# test_npf.net
KiCad netlist of a schematic drawn in Altium Designer
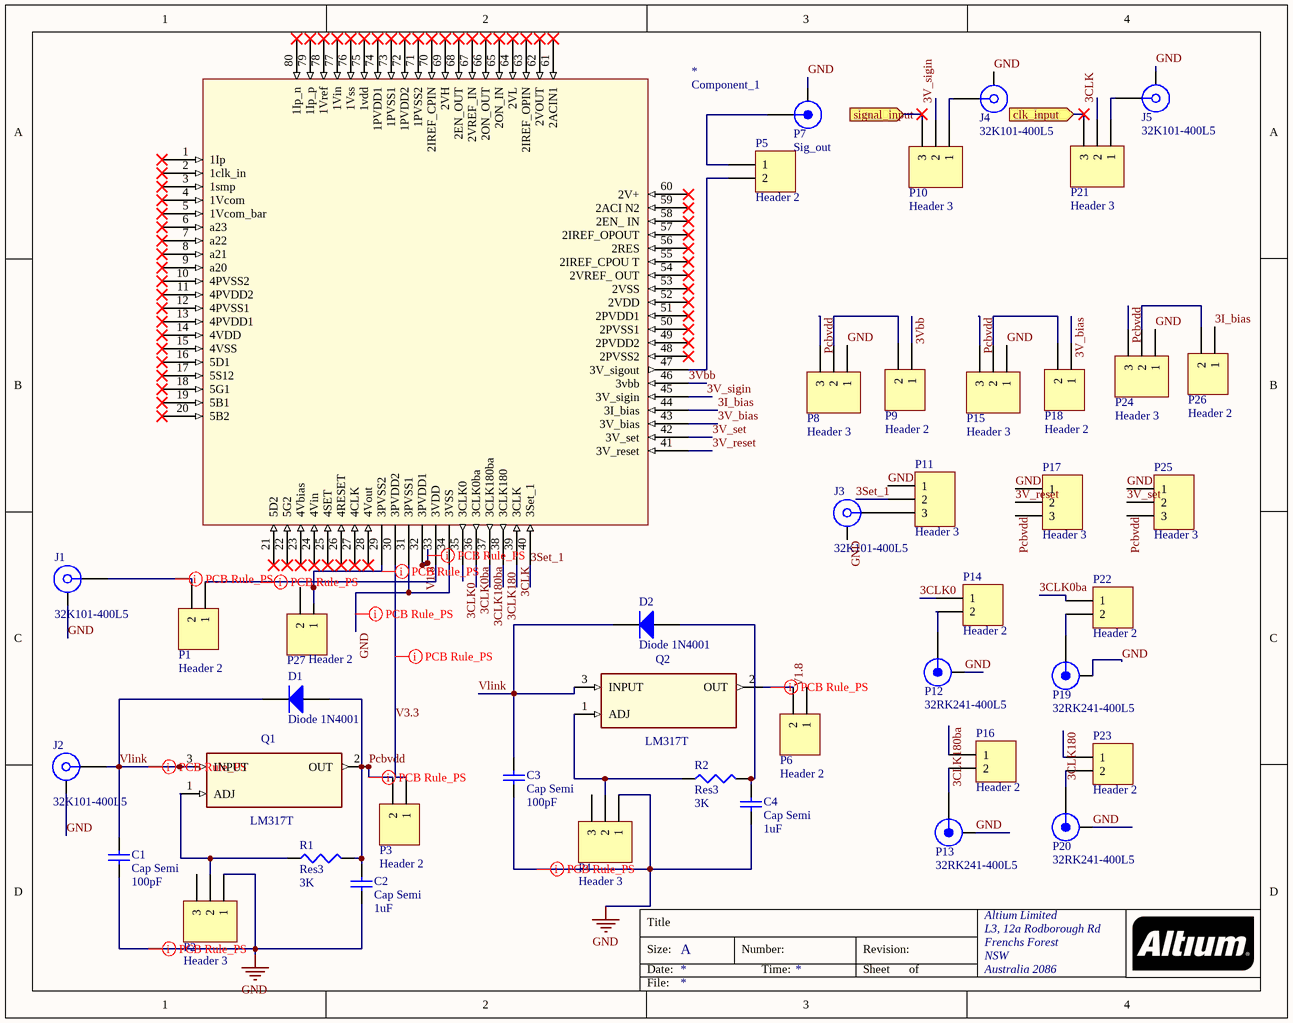
[diagram p0: test_npf.SchDoc]

(export (version "E")
  (design (tool "Eeschema 10.0.6"))
  (components
    (comp (ref "*")
      (value "Component_1")
      (footprint "LCCS50P1200X1200X85-80N")
      (libsource (lib "8pathNPF") (part "Component_1"))
    )
    (comp (ref "C1")
      (value "Cap Semi")
      (footprint "C1206")
      (description "Capacitor (Semiconductor SIM Model)")
      (fields (field (name "ALTIUM_VALUE") "100pF") (field (name "PUBLISHER") "Altium Limited"))
      (libsource (lib "Miscellaneous Devices") (part "Cap Semi"))
    )
    (comp (ref "C2")
      (value "Cap Semi")
      (footprint "C1206")
      (description "Capacitor (Semiconductor SIM Model)")
      (fields (field (name "ALTIUM_VALUE") "1uF") (field (name "PUBLISHER") "Altium Limited"))
      (libsource (lib "Miscellaneous Devices") (part "Cap Semi"))
    )
    (comp (ref "C3")
      (value "Cap Semi")
      (footprint "C1206")
      (description "Capacitor (Semiconductor SIM Model)")
      (fields (field (name "ALTIUM_VALUE") "100pF") (field (name "PUBLISHER") "Altium Limited"))
      (libsource (lib "Miscellaneous Devices") (part "Cap Semi"))
    )
    (comp (ref "C4")
      (value "Cap Semi")
      (footprint "C1206")
      (description "Capacitor (Semiconductor SIM Model)")
      (fields (field (name "ALTIUM_VALUE") "1uF") (field (name "PUBLISHER") "Altium Limited"))
      (libsource (lib "Miscellaneous Devices") (part "Cap Semi"))
    )
    (comp (ref "D1")
      (value "Diode 1N4001")
      (footprint "DO-41")
      (description "1 Amp General Purpose Rectifier")
      (fields (field (name "PUBLISHER") "Altium Limited"))
      (libsource (lib "Miscellaneous Devices") (part "Diode 1N4001"))
    )
    (comp (ref "D2")
      (value "Diode 1N4001")
      (footprint "DO-41")
      (description "1 Amp General Purpose Rectifier")
      (fields (field (name "PUBLISHER") "Altium Limited"))
      (libsource (lib "Miscellaneous Devices") (part "Diode 1N4001"))
    )
    (comp (ref "J1")
      (value "32K101-400L5")
      (footprint "ROS-32K101-400L5_V")
      (description "SMA Straight Jack, Up to 18 GHz, -55 to 155 degC")
      (libsource (lib "Rosenberger SMA") (part "32K101-400L5"))
    )
    (comp (ref "J2")
      (value "32K101-400L5")
      (footprint "ROS-32K101-400L5_V")
      (description "SMA Straight Jack, Up to 18 GHz, -55 to 155 degC")
      (libsource (lib "Rosenberger SMA") (part "32K101-400L5"))
    )
    (comp (ref "J3")
      (value "32K101-400L5")
      (footprint "ROS-32K101-400L5_V")
      (description "SMA Straight Jack, Up to 18 GHz, -55 to 155 degC")
      (libsource (lib "Rosenberger SMA") (part "32K101-400L5"))
    )
    (comp (ref "J4")
      (value "32K101-400L5")
      (footprint "ROS-32K101-400L5_V")
      (description "SMA Straight Jack, Up to 18 GHz, -55 to 155 degC")
      (libsource (lib "Rosenberger SMA") (part "32K101-400L5"))
    )
    (comp (ref "J5")
      (value "32K101-400L5")
      (footprint "ROS-32K101-400L5_V")
      (description "SMA Straight Jack, Up to 18 GHz, -55 to 155 degC")
      (libsource (lib "Rosenberger SMA") (part "32K101-400L5"))
    )
    (comp (ref "P1")
      (value "Header 2")
      (footprint "HDR1X2")
      (description "Header, 2-Pin")
      (fields (field (name "PUBLISHER") "Altium Limited"))
      (libsource (lib "") (part "Header 2_1"))
    )
    (comp (ref "P2")
      (value "Header 3")
      (footprint "HDR1X3")
      (description "Header, 3-Pin")
      (fields (field (name "PUBLISHER") "Altium Limited"))
      (libsource (lib "Miscellaneous Connectors") (part "Header 3"))
    )
    (comp (ref "P3")
      (value "Header 2")
      (footprint "HDR1X2")
      (description "Header, 2-Pin")
      (fields (field (name "PUBLISHER") "Altium Limited"))
      (libsource (lib "") (part "Header 2_1"))
    )
    (comp (ref "P4")
      (value "Header 3")
      (footprint "HDR1X3")
      (description "Header, 3-Pin")
      (fields (field (name "PUBLISHER") "Altium Limited"))
      (libsource (lib "Miscellaneous Connectors") (part "Header 3"))
    )
    (comp (ref "P5")
      (value "Header 2")
      (footprint "HDR1X2")
      (description "Header, 2-Pin")
      (fields (field (name "PUBLISHER") "Altium Limited"))
      (libsource (lib "Miscellaneous Connectors") (part "Header 2"))
    )
    (comp (ref "P6")
      (value "Header 2")
      (footprint "HDR1X2")
      (description "Header, 2-Pin")
      (fields (field (name "PUBLISHER") "Altium Limited"))
      (libsource (lib "") (part "Header 2_1"))
    )
    (comp (ref "P7")
      (value "Sig_out")
      (footprint "ROS-32K101-400L5_V")
      (description "Reverse-SMA Straight Jack, Up to 12.4 GHz, -65 to 165 degC")
      (fields (field (name "PARTNUMBER") "32RK241-400L5"))
      (libsource (lib "Rosenberger SMA") (part "32RK241-400L5"))
    )
    (comp (ref "P8")
      (value "Header 3")
      (footprint "HDR1X3")
      (description "Header, 3-Pin")
      (fields (field (name "PUBLISHER") "Altium Limited"))
      (libsource (lib "Miscellaneous Connectors") (part "Header 3"))
    )
    (comp (ref "P9")
      (value "Header 2")
      (footprint "HDR1X2")
      (description "Header, 2-Pin")
      (fields (field (name "PUBLISHER") "Altium Limited"))
      (libsource (lib "") (part "Header 2_1"))
    )
    (comp (ref "P10")
      (value "Header 3")
      (footprint "HDR1X3")
      (description "Header, 3-Pin")
      (fields (field (name "PUBLISHER") "Altium Limited"))
      (libsource (lib "Miscellaneous Connectors") (part "Header 3"))
    )
    (comp (ref "P11")
      (value "Header 3")
      (footprint "HDR1X3")
      (description "Header, 3-Pin")
      (fields (field (name "PUBLISHER") "Altium Limited"))
      (libsource (lib "") (part "Header 3_1"))
    )
    (comp (ref "P12")
      (value "32RK241-400L5")
      (footprint "ROS-32K101-400L5_V")
      (description "Reverse-SMA Straight Jack, Up to 12.4 GHz, -65 to 165 degC")
      (libsource (lib "Rosenberger SMA") (part "32RK241-400L5"))
    )
    (comp (ref "P13")
      (value "32RK241-400L5")
      (footprint "ROS-32K101-400L5_V")
      (description "Reverse-SMA Straight Jack, Up to 12.4 GHz, -65 to 165 degC")
      (libsource (lib "Rosenberger SMA") (part "32RK241-400L5"))
    )
    (comp (ref "P14")
      (value "Header 2")
      (footprint "HDR1X2")
      (description "Header, 2-Pin")
      (fields (field (name "PUBLISHER") "Altium Limited"))
      (libsource (lib "Miscellaneous Connectors") (part "Header 2"))
    )
    (comp (ref "P15")
      (value "Header 3")
      (footprint "HDR1X3")
      (description "Header, 3-Pin")
      (fields (field (name "PUBLISHER") "Altium Limited"))
      (libsource (lib "Miscellaneous Connectors") (part "Header 3"))
    )
    (comp (ref "P16")
      (value "Header 2")
      (footprint "HDR1X2")
      (description "Header, 2-Pin")
      (fields (field (name "PUBLISHER") "Altium Limited"))
      (libsource (lib "Miscellaneous Connectors") (part "Header 2"))
    )
    (comp (ref "P17")
      (value "Header 3")
      (footprint "HDR1X3")
      (description "Header, 3-Pin")
      (fields (field (name "PUBLISHER") "Altium Limited"))
      (libsource (lib "") (part "Header 3_1"))
    )
    (comp (ref "P18")
      (value "Header 2")
      (footprint "HDR1X2")
      (description "Header, 2-Pin")
      (fields (field (name "PUBLISHER") "Altium Limited"))
      (libsource (lib "") (part "Header 2_1"))
    )
    (comp (ref "P19")
      (value "32RK241-400L5")
      (footprint "ROS-32K101-400L5_V")
      (description "Reverse-SMA Straight Jack, Up to 12.4 GHz, -65 to 165 degC")
      (libsource (lib "Rosenberger SMA") (part "32RK241-400L5"))
    )
    (comp (ref "P20")
      (value "32RK241-400L5")
      (footprint "ROS-32K101-400L5_V")
      (description "Reverse-SMA Straight Jack, Up to 12.4 GHz, -65 to 165 degC")
      (libsource (lib "Rosenberger SMA") (part "32RK241-400L5"))
    )
    (comp (ref "P21")
      (value "Header 3")
      (footprint "HDR1X3")
      (description "Header, 3-Pin")
      (fields (field (name "PUBLISHER") "Altium Limited"))
      (libsource (lib "Miscellaneous Connectors") (part "Header 3"))
    )
    (comp (ref "P22")
      (value "Header 2")
      (footprint "HDR1X2")
      (description "Header, 2-Pin")
      (fields (field (name "PUBLISHER") "Altium Limited"))
      (libsource (lib "Miscellaneous Connectors") (part "Header 2"))
    )
    (comp (ref "P23")
      (value "Header 2")
      (footprint "HDR1X2")
      (description "Header, 2-Pin")
      (fields (field (name "PUBLISHER") "Altium Limited"))
      (libsource (lib "Miscellaneous Connectors") (part "Header 2"))
    )
    (comp (ref "P24")
      (value "Header 3")
      (footprint "HDR1X3")
      (description "Header, 3-Pin")
      (fields (field (name "PUBLISHER") "Altium Limited"))
      (libsource (lib "Miscellaneous Connectors") (part "Header 3"))
    )
    (comp (ref "P25")
      (value "Header 3")
      (footprint "HDR1X3")
      (description "Header, 3-Pin")
      (fields (field (name "PUBLISHER") "Altium Limited"))
      (libsource (lib "") (part "Header 3_1"))
    )
    (comp (ref "P26")
      (value "Header 2")
      (footprint "HDR1X2")
      (description "Header, 2-Pin")
      (fields (field (name "PUBLISHER") "Altium Limited"))
      (libsource (lib "") (part "Header 2_1"))
    )
    (comp (ref "P27")
      (value "Header 2")
      (footprint "HDR1X2")
      (description "Header, 2-Pin")
      (fields (field (name "PUBLISHER") "Altium Limited"))
      (libsource (lib "") (part "Header 2_1"))
    )
    (comp (ref "Q1")
      (value "LM317T")
      (footprint "TO254P450X1020X2000-3P")
      (description "LM317 Series 40 Vin 1.5 A Adjustable Positive Voltage Regulator - TO-220-3")
      (fields (field (name "MF") "Texas Instruments"))
      (libsource (lib "LM317T") (part "LM317T"))
    )
    (comp (ref "Q2")
      (value "LM317T")
      (footprint "TO254P450X1020X2000-3P")
      (description "LM317 Series 40 Vin 1.5 A Adjustable Positive Voltage Regulator - TO-220-3")
      (fields (field (name "MF") "Texas Instruments"))
      (libsource (lib "LM317T") (part "LM317T"))
    )
    (comp (ref "R1")
      (value "Res3")
      (footprint "J1-0603")
      (description "Resistor")
      (fields (field (name "ALTIUM_VALUE") "3K") (field (name "PUBLISHER") "Altium Limited"))
      (libsource (lib "Miscellaneous Devices") (part "Res3"))
    )
    (comp (ref "R2")
      (value "Res3")
      (footprint "J1-0603")
      (description "Resistor")
      (fields (field (name "ALTIUM_VALUE") "3K") (field (name "PUBLISHER") "Altium Limited"))
      (libsource (lib "Miscellaneous Devices") (part "Res3"))
    )
  )
  (nets
    (net (code "1") (name "/3CLK") (class "Default")
      (node (ref "*") (pin "39") (pinfunction "3CLK_39") (pintype "input"))
      (node (ref "P21") (pin "2") (pinfunction "2_2") (pintype "passive"))
    )
    (net (code "2") (name "/3CLK0") (class "Default")
      (node (ref "*") (pin "35") (pinfunction "3CLK0_35") (pintype "output"))
      (node (ref "P14") (pin "1") (pinfunction "1_1") (pintype "passive"))
    )
    (net (code "3") (name "/3CLK0ba") (class "Default")
      (node (ref "*") (pin "36") (pinfunction "3CLK0ba_36") (pintype "output"))
      (node (ref "P22") (pin "1") (pinfunction "1_1") (pintype "passive"))
    )
    (net (code "4") (name "/3CLK180") (class "Default")
      (node (ref "*") (pin "38") (pinfunction "3CLK180_38") (pintype "output"))
      (node (ref "P23") (pin "1") (pinfunction "1_1") (pintype "passive"))
    )
    (net (code "5") (name "/3CLK180ba") (class "Default")
      (node (ref "*") (pin "37") (pinfunction "3CLK180ba_37") (pintype "output"))
      (node (ref "P16") (pin "1") (pinfunction "1_1") (pintype "passive"))
    )
    (net (code "6") (name "/3I_bias") (class "Default")
      (node (ref "*") (pin "44") (pinfunction "3I_bias_44") (pintype "input"))
      (node (ref "P26") (pin "1") (pinfunction "1_1") (pintype "passive"))
    )
    (net (code "7") (name "/3Set_1") (class "Default")
      (node (ref "*") (pin "40") (pinfunction "3Set_1_40") (pintype "input"))
      (node (ref "P11") (pin "2") (pinfunction "2_2") (pintype "passive"))
    )
    (net (code "8") (name "/3V_bias") (class "Default")
      (node (ref "*") (pin "43") (pinfunction "3V_bias_43") (pintype "input"))
      (node (ref "P18") (pin "1") (pinfunction "1_1") (pintype "passive"))
    )
    (net (code "9") (name "/3V_reset") (class "Default")
      (node (ref "*") (pin "41") (pinfunction "3V_reset_41") (pintype "input"))
      (node (ref "P17") (pin "2") (pinfunction "2_2") (pintype "passive"))
    )
    (net (code "10") (name "/3V_set") (class "Default")
      (node (ref "*") (pin "42") (pinfunction "3V_set_42") (pintype "input"))
      (node (ref "P25") (pin "2") (pinfunction "2_2") (pintype "passive"))
    )
    (net (code "11") (name "/3V_sigin") (class "Default")
      (node (ref "*") (pin "45") (pinfunction "3V_sigin_45") (pintype "input"))
      (node (ref "P10") (pin "2") (pinfunction "2_2") (pintype "passive"))
    )
    (net (code "12") (name "/3Vbb") (class "Default")
      (node (ref "*") (pin "46") (pinfunction "3vbb_46") (pintype "input"))
      (node (ref "P9") (pin "1") (pinfunction "1_1") (pintype "passive"))
    )
    (net (code "13") (name "/Pcbvdd") (class "Default")
      (node (ref "C2") (pin "2") (pinfunction "2_2") (pintype "passive"))
      (node (ref "D1") (pin "1") (pinfunction "A_1") (pintype "passive"))
      (node (ref "P15") (pin "3") (pinfunction "3_3") (pintype "passive"))
      (node (ref "P17") (pin "3") (pinfunction "3_3") (pintype "passive"))
      (node (ref "P24") (pin "3") (pinfunction "3_3") (pintype "passive"))
      (node (ref "P25") (pin "3") (pinfunction "3_3") (pintype "passive"))
      (node (ref "P3") (pin "2") (pinfunction "2_2") (pintype "passive"))
      (node (ref "P8") (pin "3") (pinfunction "3_3") (pintype "passive"))
      (node (ref "Q1") (pin "2") (pinfunction "OUT_2") (pintype "output"))
      (node (ref "R1") (pin "2") (pinfunction "2_2") (pintype "passive"))
    )
    (net (code "14") (name "/V1.8") (class "Default")
      (node (ref "*") (pin "32") (pinfunction "3PVDD1_32") (pintype "power_in"))
      (node (ref "P6") (pin "1") (pinfunction "1_1") (pintype "passive"))
    )
    (net (code "15") (name "/V3.3") (class "Default")
      (node (ref "*") (pin "30") (pinfunction "3PVDD2_30") (pintype "power_in"))
      (node (ref "P3") (pin "1") (pinfunction "1_1") (pintype "passive"))
    )
    (net (code "16") (name "/Vlink") (class "Default")
      (node (ref "C1") (pin "2") (pinfunction "2_2") (pintype "passive"))
      (node (ref "C3") (pin "2") (pinfunction "2_2") (pintype "passive"))
      (node (ref "D1") (pin "2") (pinfunction "K_2") (pintype "passive"))
      (node (ref "D2") (pin "2") (pinfunction "K_2") (pintype "passive"))
      (node (ref "J2") (pin "1") (pinfunction "1_1") (pintype "passive"))
      (node (ref "Q1") (pin "3") (pinfunction "INPUT_3") (pintype "input"))
      (node (ref "Q2") (pin "3") (pinfunction "INPUT_3") (pintype "input"))
    )
    (net (code "17") (name "/clk_input") (class "Default")
      (node (ref "P21") (pin "3") (pinfunction "3_3") (pintype "passive+no_connect"))
    )
    (net (code "18") (name "/signal_input") (class "Default")
      (node (ref "P10") (pin "3") (pinfunction "3_3") (pintype "passive+no_connect"))
    )
    (net (code "19") (name "GND") (class "Default")
      (node (ref "*") (pin "31") (pinfunction "3PVSS1_31") (pintype "power_in"))
      (node (ref "*") (pin "34") (pinfunction "3VSS_34") (pintype "power_in"))
      (node (ref "C1") (pin "1") (pinfunction "1_1") (pintype "passive"))
      (node (ref "C2") (pin "1") (pinfunction "1_1") (pintype "passive"))
      (node (ref "C3") (pin "1") (pinfunction "1_1") (pintype "passive"))
      (node (ref "C4") (pin "1") (pinfunction "1_1") (pintype "passive"))
      (node (ref "J1") (pin "MH") (pinfunction "MH_MH") (pintype "passive"))
      (node (ref "J2") (pin "MH") (pinfunction "MH_MH") (pintype "passive"))
      (node (ref "J3") (pin "MH") (pinfunction "MH_MH") (pintype "passive"))
      (node (ref "J4") (pin "MH") (pinfunction "MH_MH") (pintype "passive"))
      (node (ref "J5") (pin "MH") (pinfunction "MH_MH") (pintype "passive"))
      (node (ref "P11") (pin "1") (pinfunction "1_1") (pintype "passive"))
      (node (ref "P12") (pin "MH") (pinfunction "MH_MH") (pintype "passive"))
      (node (ref "P13") (pin "MH") (pinfunction "MH_MH") (pintype "passive"))
      (node (ref "P15") (pin "1") (pinfunction "1_1") (pintype "passive"))
      (node (ref "P17") (pin "1") (pinfunction "1_1") (pintype "passive"))
      (node (ref "P19") (pin "MH") (pinfunction "MH_MH") (pintype "passive"))
      (node (ref "P2") (pin "1") (pinfunction "1_1") (pintype "passive"))
      (node (ref "P20") (pin "MH") (pinfunction "MH_MH") (pintype "passive"))
      (node (ref "P24") (pin "1") (pinfunction "1_1") (pintype "passive"))
      (node (ref "P25") (pin "1") (pinfunction "1_1") (pintype "passive"))
      (node (ref "P4") (pin "1") (pinfunction "1_1") (pintype "passive"))
      (node (ref "P7") (pin "MH") (pinfunction "MH_MH") (pintype "passive"))
      (node (ref "P8") (pin "1") (pinfunction "1_1") (pintype "passive"))
    )
    (net (code "20") (name "Net-(*-3PVSS2)") (class "Default")
      (node (ref "*") (pin "29") (pinfunction "3PVSS2_29") (pintype "power_in"))
      (node (ref "P27") (pin "1") (pinfunction "1_1") (pintype "passive"))
    )
    (net (code "21") (name "Net-(*-3VDD)") (class "Default")
      (node (ref "*") (pin "33") (pinfunction "3VDD_33") (pintype "power_in"))
      (node (ref "P1") (pin "1") (pinfunction "1_1") (pintype "passive"))
    )
    (net (code "22") (name "Net-(*-3V_sigout)") (class "Default")
      (node (ref "*") (pin "47") (pinfunction "3V_sigout_47") (pintype "output"))
      (node (ref "P5") (pin "2") (pinfunction "2_2") (pintype "passive"))
    )
    (net (code "23") (name "Net-(D2-A)") (class "Default")
      (node (ref "C4") (pin "2") (pinfunction "2_2") (pintype "passive"))
      (node (ref "D2") (pin "1") (pinfunction "A_1") (pintype "passive"))
      (node (ref "R2") (pin "2") (pinfunction "2_2") (pintype "passive"))
    )
    (net (code "24") (name "Net-(J1-Pad1)") (class "Default")
      (node (ref "J1") (pin "1") (pinfunction "1_1") (pintype "passive"))
      (node (ref "P1") (pin "2") (pinfunction "2_2") (pintype "passive"))
    )
    (net (code "25") (name "Net-(J3-Pad1)") (class "Default")
      (node (ref "J3") (pin "1") (pinfunction "1_1") (pintype "passive"))
      (node (ref "P11") (pin "3") (pinfunction "3_3") (pintype "passive"))
    )
    (net (code "26") (name "Net-(J4-Pad1)") (class "Default")
      (node (ref "J4") (pin "1") (pinfunction "1_1") (pintype "passive"))
      (node (ref "P10") (pin "1") (pinfunction "1_1") (pintype "passive"))
    )
    (net (code "27") (name "Net-(J5-Pad1)") (class "Default")
      (node (ref "J5") (pin "1") (pinfunction "1_1") (pintype "passive"))
      (node (ref "P21") (pin "1") (pinfunction "1_1") (pintype "passive"))
    )
    (net (code "28") (name "Net-(P5-Pad1)") (class "Default")
      (node (ref "P5") (pin "1") (pinfunction "1_1") (pintype "passive"))
      (node (ref "P7") (pin "1") (pinfunction "1_1") (pintype "passive"))
    )
    (net (code "29") (name "Net-(P8-Pad2)") (class "Default")
      (node (ref "P8") (pin "2") (pinfunction "2_2") (pintype "passive"))
      (node (ref "P9") (pin "2") (pinfunction "2_2") (pintype "passive"))
    )
    (net (code "30") (name "Net-(P12-Pad1)") (class "Default")
      (node (ref "P12") (pin "1") (pinfunction "1_1") (pintype "passive"))
      (node (ref "P14") (pin "2") (pinfunction "2_2") (pintype "passive"))
    )
    (net (code "31") (name "Net-(P13-Pad1)") (class "Default")
      (node (ref "P13") (pin "1") (pinfunction "1_1") (pintype "passive"))
      (node (ref "P16") (pin "2") (pinfunction "2_2") (pintype "passive"))
    )
    (net (code "32") (name "Net-(P15-Pad2)") (class "Default")
      (node (ref "P15") (pin "2") (pinfunction "2_2") (pintype "passive"))
      (node (ref "P18") (pin "2") (pinfunction "2_2") (pintype "passive"))
    )
    (net (code "33") (name "Net-(P19-Pad1)") (class "Default")
      (node (ref "P19") (pin "1") (pinfunction "1_1") (pintype "passive"))
      (node (ref "P22") (pin "2") (pinfunction "2_2") (pintype "passive"))
    )
    (net (code "34") (name "Net-(P20-Pad1)") (class "Default")
      (node (ref "P20") (pin "1") (pinfunction "1_1") (pintype "passive"))
      (node (ref "P23") (pin "2") (pinfunction "2_2") (pintype "passive"))
    )
    (net (code "35") (name "Net-(P24-Pad2)") (class "Default")
      (node (ref "P24") (pin "2") (pinfunction "2_2") (pintype "passive"))
      (node (ref "P26") (pin "2") (pinfunction "2_2") (pintype "passive"))
    )
    (net (code "36") (name "Net-(Q1-ADJ)") (class "Default")
      (node (ref "P2") (pin "2") (pinfunction "2_2") (pintype "passive"))
      (node (ref "Q1") (pin "1") (pinfunction "ADJ_1") (pintype "input"))
      (node (ref "R1") (pin "1") (pinfunction "1_1") (pintype "passive"))
    )
    (net (code "37") (name "Net-(Q2-ADJ)") (class "Default")
      (node (ref "P4") (pin "2") (pinfunction "2_2") (pintype "passive"))
      (node (ref "Q2") (pin "1") (pinfunction "ADJ_1") (pintype "input"))
      (node (ref "R2") (pin "1") (pinfunction "1_1") (pintype "passive"))
    )
    (net (code "38") (name "Net-(Q2-OUT)") (class "Default")
      (node (ref "P6") (pin "2") (pinfunction "2_2") (pintype "passive"))
      (node (ref "Q2") (pin "2") (pinfunction "OUT_2") (pintype "output"))
    )
    (net (code "39") (name "unconnected-(*-1Ip-Pad1)") (class "Default")
      (node (ref "*") (pin "1") (pinfunction "1Ip_1") (pintype "input+no_connect"))
    )
    (net (code "40") (name "unconnected-(*-1Ip_n-Pad80)") (class "Default")
      (node (ref "*") (pin "80") (pinfunction "1Ip_n_80") (pintype "input+no_connect"))
    )
    (net (code "41") (name "unconnected-(*-1Ip_p-Pad79)") (class "Default")
      (node (ref "*") (pin "79") (pinfunction "1Ip_p_79") (pintype "input+no_connect"))
    )
    (net (code "42") (name "unconnected-(*-1PVDD1-Pad74)") (class "Default")
      (node (ref "*") (pin "74") (pinfunction "1PVDD1_74") (pintype "input+no_connect"))
    )
    (net (code "43") (name "unconnected-(*-1PVDD2-Pad72)") (class "Default")
      (node (ref "*") (pin "72") (pinfunction "1PVDD2_72") (pintype "input+no_connect"))
    )
    (net (code "44") (name "unconnected-(*-1PVSS1-Pad73)") (class "Default")
      (node (ref "*") (pin "73") (pinfunction "1PVSS1_73") (pintype "input+no_connect"))
    )
    (net (code "45") (name "unconnected-(*-1PVSS2-Pad71)") (class "Default")
      (node (ref "*") (pin "71") (pinfunction "1PVSS2_71") (pintype "input+no_connect"))
    )
    (net (code "46") (name "unconnected-(*-1Vcom-Pad4)") (class "Default")
      (node (ref "*") (pin "4") (pinfunction "1Vcom_4") (pintype "input+no_connect"))
    )
    (net (code "47") (name "unconnected-(*-1Vcom_bar-Pad5)") (class "Default")
      (node (ref "*") (pin "5") (pinfunction "1Vcom_bar_5") (pintype "input+no_connect"))
    )
    (net (code "48") (name "unconnected-(*-1Vin-Pad77)") (class "Default")
      (node (ref "*") (pin "77") (pinfunction "1Vin_77") (pintype "input+no_connect"))
    )
    (net (code "49") (name "unconnected-(*-1Vref-Pad78)") (class "Default")
      (node (ref "*") (pin "78") (pinfunction "1Vref_78") (pintype "input+no_connect"))
    )
    (net (code "50") (name "unconnected-(*-1Vss-Pad76)") (class "Default")
      (node (ref "*") (pin "76") (pinfunction "1Vss_76") (pintype "input+no_connect"))
    )
    (net (code "51") (name "unconnected-(*-1clk_in-Pad2)") (class "Default")
      (node (ref "*") (pin "2") (pinfunction "1clk_in_2") (pintype "input+no_connect"))
    )
    (net (code "52") (name "unconnected-(*-1smp-Pad3)") (class "Default")
      (node (ref "*") (pin "3") (pinfunction "1smp_3") (pintype "input+no_connect"))
    )
    (net (code "53") (name "unconnected-(*-1vdd-Pad75)") (class "Default")
      (node (ref "*") (pin "75") (pinfunction "1vdd_75") (pintype "input+no_connect"))
    )
    (net (code "54") (name "unconnected-(*-2ACIN1-Pad61)") (class "Default")
      (node (ref "*") (pin "61") (pinfunction "2ACIN1_61") (pintype "input+no_connect"))
    )
    (net (code "55") (name "unconnected-(*-2ACI_N2-Pad59)") (class "Default")
      (node (ref "*") (pin "59") (pinfunction "2ACI_N2_59") (pintype "input+no_connect"))
    )
    (net (code "56") (name "unconnected-(*-2EN_OUT-Pad68)") (class "Default")
      (node (ref "*") (pin "68") (pinfunction "2EN_OUT_68") (pintype "input+no_connect"))
    )
    (net (code "57") (name "unconnected-(*-2EN__IN-Pad58)") (class "Default")
      (node (ref "*") (pin "58") (pinfunction "2EN__IN_58") (pintype "input+no_connect"))
    )
    (net (code "58") (name "unconnected-(*-2IREF_CPIN-Pad70)") (class "Default")
      (node (ref "*") (pin "70") (pinfunction "2IREF_CPIN_70") (pintype "input+no_connect"))
    )
    (net (code "59") (name "unconnected-(*-2IREF_CPOU_T-Pad55)") (class "Default")
      (node (ref "*") (pin "55") (pinfunction "2IREF_CPOU_T_55") (pintype "input+no_connect"))
    )
    (net (code "60") (name "unconnected-(*-2IREF_OPIN-Pad63)") (class "Default")
      (node (ref "*") (pin "63") (pinfunction "2IREF_OPIN_63") (pintype "input+no_connect"))
    )
    (net (code "61") (name "unconnected-(*-2IREF_OPOUT-Pad57)") (class "Default")
      (node (ref "*") (pin "57") (pinfunction "2IREF_OPOUT_57") (pintype "input+no_connect"))
    )
    (net (code "62") (name "unconnected-(*-2ON_IN-Pad65)") (class "Default")
      (node (ref "*") (pin "65") (pinfunction "2ON_IN_65") (pintype "input+no_connect"))
    )
    (net (code "63") (name "unconnected-(*-2ON_OUT-Pad66)") (class "Default")
      (node (ref "*") (pin "66") (pinfunction "2ON_OUT_66") (pintype "input+no_connect"))
    )
    (net (code "64") (name "unconnected-(*-2PVDD1-Pad51)") (class "Default")
      (node (ref "*") (pin "51") (pinfunction "2PVDD1_51") (pintype "input+no_connect"))
    )
    (net (code "65") (name "unconnected-(*-2PVDD2-Pad49)") (class "Default")
      (node (ref "*") (pin "49") (pinfunction "2PVDD2_49") (pintype "input+no_connect"))
    )
    (net (code "66") (name "unconnected-(*-2PVSS1-Pad50)") (class "Default")
      (node (ref "*") (pin "50") (pinfunction "2PVSS1_50") (pintype "input+no_connect"))
    )
    (net (code "67") (name "unconnected-(*-2PVSS2-Pad48)") (class "Default")
      (node (ref "*") (pin "48") (pinfunction "2PVSS2_48") (pintype "input+no_connect"))
    )
    (net (code "68") (name "unconnected-(*-2RES-Pad56)") (class "Default")
      (node (ref "*") (pin "56") (pinfunction "2RES_56") (pintype "input+no_connect"))
    )
    (net (code "69") (name "unconnected-(*-2V+-Pad60)") (class "Default")
      (node (ref "*") (pin "60") (pinfunction "2V+_60") (pintype "input+no_connect"))
    )
    (net (code "70") (name "unconnected-(*-2VDD-Pad52)") (class "Default")
      (node (ref "*") (pin "52") (pinfunction "2VDD_52") (pintype "input+no_connect"))
    )
    (net (code "71") (name "unconnected-(*-2VH-Pad69)") (class "Default")
      (node (ref "*") (pin "69") (pinfunction "2VH_69") (pintype "input+no_connect"))
    )
    (net (code "72") (name "unconnected-(*-2VL-Pad64)") (class "Default")
      (node (ref "*") (pin "64") (pinfunction "2VL_64") (pintype "input+no_connect"))
    )
    (net (code "73") (name "unconnected-(*-2VOUT-Pad62)") (class "Default")
      (node (ref "*") (pin "62") (pinfunction "2VOUT_62") (pintype "input+no_connect"))
    )
    (net (code "74") (name "unconnected-(*-2VREF_IN-Pad67)") (class "Default")
      (node (ref "*") (pin "67") (pinfunction "2VREF_IN_67") (pintype "input+no_connect"))
    )
    (net (code "75") (name "unconnected-(*-2VREF__OUT-Pad54)") (class "Default")
      (node (ref "*") (pin "54") (pinfunction "2VREF__OUT_54") (pintype "input+no_connect"))
    )
    (net (code "76") (name "unconnected-(*-2VSS-Pad53)") (class "Default")
      (node (ref "*") (pin "53") (pinfunction "2VSS_53") (pintype "input+no_connect"))
    )
    (net (code "77") (name "unconnected-(*-4CLK-Pad27)") (class "Default")
      (node (ref "*") (pin "27") (pinfunction "4CLK_27") (pintype "input+no_connect"))
    )
    (net (code "78") (name "unconnected-(*-4PVDD1-Pad13)") (class "Default")
      (node (ref "*") (pin "13") (pinfunction "4PVDD1_13") (pintype "input+no_connect"))
    )
    (net (code "79") (name "unconnected-(*-4PVDD2-Pad11)") (class "Default")
      (node (ref "*") (pin "11") (pinfunction "4PVDD2_11") (pintype "input+no_connect"))
    )
    (net (code "80") (name "unconnected-(*-4PVSS1-Pad12)") (class "Default")
      (node (ref "*") (pin "12") (pinfunction "4PVSS1_12") (pintype "input+no_connect"))
    )
    (net (code "81") (name "unconnected-(*-4PVSS2-Pad10)") (class "Default")
      (node (ref "*") (pin "10") (pinfunction "4PVSS2_10") (pintype "input+no_connect"))
    )
    (net (code "82") (name "unconnected-(*-4RESET-Pad26)") (class "Default")
      (node (ref "*") (pin "26") (pinfunction "4RESET_26") (pintype "input+no_connect"))
    )
    (net (code "83") (name "unconnected-(*-4SET-Pad25)") (class "Default")
      (node (ref "*") (pin "25") (pinfunction "4SET_25") (pintype "input+no_connect"))
    )
    (net (code "84") (name "unconnected-(*-4VDD-Pad14)") (class "Default")
      (node (ref "*") (pin "14") (pinfunction "4VDD_14") (pintype "input+no_connect"))
    )
    (net (code "85") (name "unconnected-(*-4VSS-Pad15)") (class "Default")
      (node (ref "*") (pin "15") (pinfunction "4VSS_15") (pintype "input+no_connect"))
    )
    (net (code "86") (name "unconnected-(*-4Vbias-Pad23)") (class "Default")
      (node (ref "*") (pin "23") (pinfunction "4Vbias_23") (pintype "input+no_connect"))
    )
    (net (code "87") (name "unconnected-(*-4Vin-Pad24)") (class "Default")
      (node (ref "*") (pin "24") (pinfunction "4Vin_24") (pintype "input+no_connect"))
    )
    (net (code "88") (name "unconnected-(*-4Vout-Pad28)") (class "Default")
      (node (ref "*") (pin "28") (pinfunction "4Vout_28") (pintype "input+no_connect"))
    )
    (net (code "89") (name "unconnected-(*-5B1-Pad19)") (class "Default")
      (node (ref "*") (pin "19") (pinfunction "5B1_19") (pintype "input+no_connect"))
    )
    (net (code "90") (name "unconnected-(*-5B2-Pad20)") (class "Default")
      (node (ref "*") (pin "20") (pinfunction "5B2_20") (pintype "input+no_connect"))
    )
    (net (code "91") (name "unconnected-(*-5D1-Pad16)") (class "Default")
      (node (ref "*") (pin "16") (pinfunction "5D1_16") (pintype "input+no_connect"))
    )
    (net (code "92") (name "unconnected-(*-5D2-Pad21)") (class "Default")
      (node (ref "*") (pin "21") (pinfunction "5D2_21") (pintype "input+no_connect"))
    )
    (net (code "93") (name "unconnected-(*-5G1-Pad18)") (class "Default")
      (node (ref "*") (pin "18") (pinfunction "5G1_18") (pintype "input+no_connect"))
    )
    (net (code "94") (name "unconnected-(*-5G2-Pad22)") (class "Default")
      (node (ref "*") (pin "22") (pinfunction "5G2_22") (pintype "input+no_connect"))
    )
    (net (code "95") (name "unconnected-(*-5S12-Pad17)") (class "Default")
      (node (ref "*") (pin "17") (pinfunction "5S12_17") (pintype "input+no_connect"))
    )
    (net (code "96") (name "unconnected-(*-a20-Pad9)") (class "Default")
      (node (ref "*") (pin "9") (pinfunction "a20_9") (pintype "input+no_connect"))
    )
    (net (code "97") (name "unconnected-(*-a21-Pad8)") (class "Default")
      (node (ref "*") (pin "8") (pinfunction "a21_8") (pintype "input+no_connect"))
    )
    (net (code "98") (name "unconnected-(*-a22-Pad7)") (class "Default")
      (node (ref "*") (pin "7") (pinfunction "a22_7") (pintype "input+no_connect"))
    )
    (net (code "99") (name "unconnected-(*-a23-Pad6)") (class "Default")
      (node (ref "*") (pin "6") (pinfunction "a23_6") (pintype "input+no_connect"))
    )
    (net (code "100") (name "unconnected-(P2-Pad3)") (class "Default")
      (node (ref "P2") (pin "3") (pinfunction "3_3") (pintype "passive"))
    )
    (net (code "101") (name "unconnected-(P4-Pad3)") (class "Default")
      (node (ref "P4") (pin "3") (pinfunction "3_3") (pintype "passive"))
    )
    (net (code "102") (name "unconnected-(P27-Pad2)") (class "Default")
      (node (ref "P27") (pin "2") (pinfunction "2_2") (pintype "passive"))
    )
  )
)
